# nusense-monitors.net
KiCad netlist of a schematic drawn in Altium Designer
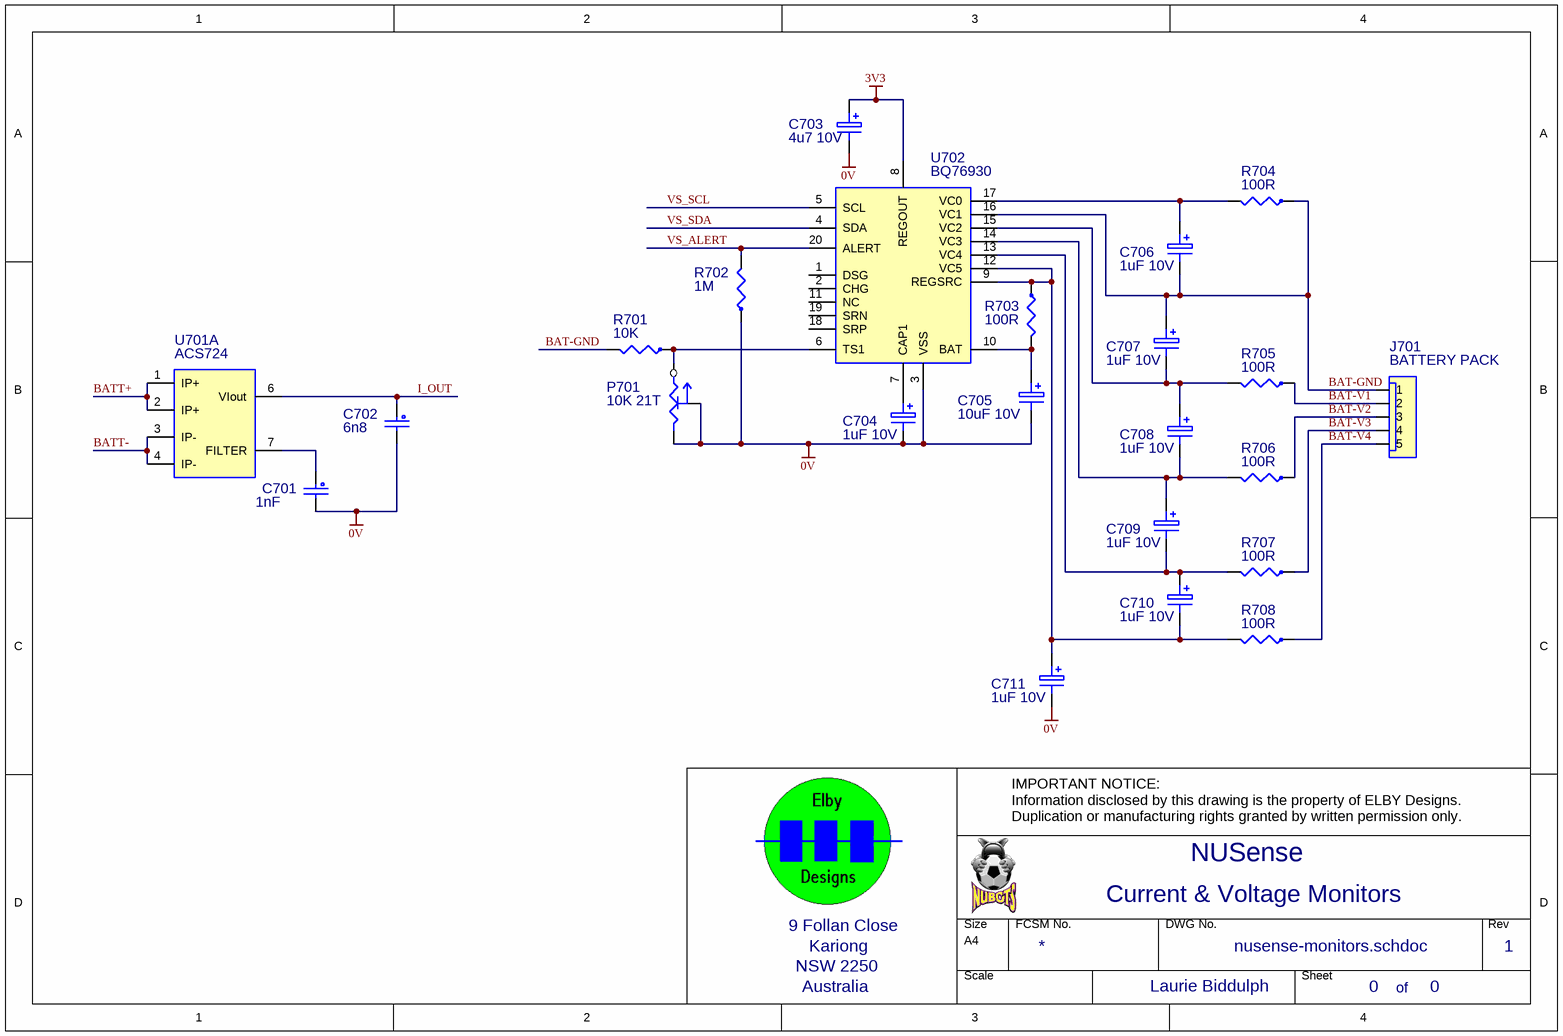
[diagram p0: nusense-monitors.schdoc]

(export (version "E")
  (design (tool "Eeschema 10.0.6"))
  (components
    (comp (ref "C701")
      (value "1nF")
      (footprint "RAD-0.2(LB)")
      (description "63V 10% Metallised Polyester")
      (libsource (lib "capacitor") (part "CP-1NF(LB)"))
    )
    (comp (ref "C702")
      (value "6n8")
      (footprint "RAD-0.2(LB)")
      (description "63V 10% Metallised Polyester")
      (libsource (lib "capacitor") (part "CP-6N8F(LB)"))
    )
    (comp (ref "C703")
      (value "4u7 10V")
      (footprint "RB-D5.0-P2.0")
      (description "20% 50V Aluminium Electrolytic")
      (libsource (lib "capacitor") (part "CE-4U7F50V(LB)"))
    )
    (comp (ref "C704")
      (value "1uF 10V")
      (footprint "RB-D5.0-P2.0")
      (description "20% 50V Aluminium Electrolytic")
      (libsource (lib "capacitor") (part "CE-1UF50V(LB)"))
    )
    (comp (ref "C705")
      (value "10uF 10V")
      (footprint "RB-D6.3-P2.5")
      (description "20% 50V Aluminium Electrolytic")
      (libsource (lib "capacitor") (part "CE-10UF50V(LB)"))
    )
    (comp (ref "C706")
      (value "1uF 10V")
      (footprint "RB-D5.0-P2.0")
      (description "20% 50V Aluminium Electrolytic")
      (libsource (lib "capacitor") (part "CE-1UF50V(LB)"))
    )
    (comp (ref "C707")
      (value "1uF 10V")
      (footprint "RB-D5.0-P2.0")
      (description "20% 50V Aluminium Electrolytic")
      (libsource (lib "capacitor") (part "CE-1UF50V(LB)"))
    )
    (comp (ref "C708")
      (value "1uF 10V")
      (footprint "RB-D5.0-P2.0")
      (description "20% 50V Aluminium Electrolytic")
      (libsource (lib "capacitor") (part "CE-1UF50V(LB)"))
    )
    (comp (ref "C709")
      (value "1uF 10V")
      (footprint "RB-D5.0-P2.0")
      (description "20% 50V Aluminium Electrolytic")
      (libsource (lib "capacitor") (part "CE-1UF50V(LB)"))
    )
    (comp (ref "C710")
      (value "1uF 10V")
      (footprint "RB-D5.0-P2.0")
      (description "20% 50V Aluminium Electrolytic")
      (libsource (lib "capacitor") (part "CE-1UF50V(LB)"))
    )
    (comp (ref "C711")
      (value "1uF 10V")
      (footprint "RB-D5.0-P2.0")
      (description "20% 50V Aluminium Electrolytic")
      (libsource (lib "capacitor") (part "CE-1UF50V(LB)"))
    )
    (comp (ref "J701")
      (value "BATTERY PACK")
      (footprint "MTA-5V(LB)")
      (libsource (lib "connectors") (part "MTA-5V(LB)"))
    )
    (comp (ref "P701")
      (value "10K 21T")
      (footprint "TRIMPOT(LB)")
      (description "Multiturn Trimpot (Spectrol 64W)")
      (libsource (lib "potentiometer") (part "RT-10K(LB)"))
    )
    (comp (ref "R701")
      (value "10K")
      (footprint "AXIAL-0.4(LB)")
      (description "0.5W 1% Metal Film Resistor")
      (libsource (lib "resistor") (part "RM-10K(LB)"))
    )
    (comp (ref "R702")
      (value "1M")
      (footprint "AXIAL-0.4(LB)")
      (description "0.5W 1% Metal Film Resistor")
      (libsource (lib "resistor") (part "RM-1M(LB)"))
    )
    (comp (ref "R703")
      (value "100R")
      (footprint "AXIAL-0.4(LB)")
      (description "0.5W 1% Metal Film Resistor")
      (libsource (lib "resistor") (part "RM-100R(LB)"))
    )
    (comp (ref "R704")
      (value "100R")
      (footprint "AXIAL-0.4(LB)")
      (description "0.5W 1% Metal Film Resistor")
      (libsource (lib "resistor") (part "RM-100R(LB)"))
    )
    (comp (ref "R705")
      (value "100R")
      (footprint "AXIAL-0.4(LB)")
      (description "0.5W 1% Metal Film Resistor")
      (libsource (lib "resistor") (part "RM-100R(LB)"))
    )
    (comp (ref "R706")
      (value "100R")
      (footprint "AXIAL-0.4(LB)")
      (description "0.5W 1% Metal Film Resistor")
      (libsource (lib "resistor") (part "RM-100R(LB)"))
    )
    (comp (ref "R707")
      (value "100R")
      (footprint "AXIAL-0.4(LB)")
      (description "0.5W 1% Metal Film Resistor")
      (libsource (lib "resistor") (part "RM-100R(LB)"))
    )
    (comp (ref "R708")
      (value "100R")
      (footprint "AXIAL-0.4(LB)")
      (description "0.5W 1% Metal Film Resistor")
      (libsource (lib "resistor") (part "RM-100R(LB)"))
    )
    (comp (ref "U701")
      (value "ACS724")
      (description "Current Monitor")
      (libsource (lib "NuBots") (part "ACS724"))
    )
    (comp (ref "U702")
      (value "BQ76930")
      (description "Battery Monitor")
      (libsource (lib "NuBots") (part "BQ76930"))
    )
  )
  (nets
    (net (code "1") (name "/BAT-GND") (class "Default")
      (node (ref "C706") (pin "2") (pintype "passive"))
      (node (ref "C707") (pin "1") (pintype "passive"))
      (node (ref "J701") (pin "1") (pinfunction "1_1") (pintype "passive"))
      (node (ref "R701") (pin "2") (pinfunction "2_2") (pintype "passive"))
      (node (ref "R704") (pin "1") (pinfunction "1_1") (pintype "passive"))
      (node (ref "U702") (pin "16") (pinfunction "VC1_16") (pintype "passive"))
    )
    (net (code "2") (name "/BAT-V1") (class "Default")
      (node (ref "J701") (pin "2") (pinfunction "2_2") (pintype "passive"))
      (node (ref "R705") (pin "1") (pinfunction "1_1") (pintype "passive"))
    )
    (net (code "3") (name "/BAT-V2") (class "Default")
      (node (ref "J701") (pin "3") (pinfunction "3_3") (pintype "passive"))
      (node (ref "R706") (pin "1") (pinfunction "1_1") (pintype "passive"))
    )
    (net (code "4") (name "/BAT-V3") (class "Default")
      (node (ref "J701") (pin "4") (pinfunction "4_4") (pintype "passive"))
      (node (ref "R707") (pin "1") (pinfunction "1_1") (pintype "passive"))
    )
    (net (code "5") (name "/BAT-V4") (class "Default")
      (node (ref "J701") (pin "5") (pinfunction "5_5") (pintype "passive"))
      (node (ref "R708") (pin "1") (pinfunction "1_1") (pintype "passive"))
    )
    (net (code "6") (name "/BATT+") (class "Default")
      (node (ref "U701") (pin "1") (pinfunction "IP+_1") (pintype "passive"))
      (node (ref "U701") (pin "2") (pinfunction "IP+_2") (pintype "passive"))
    )
    (net (code "7") (name "/BATT-") (class "Default")
      (node (ref "U701") (pin "3") (pinfunction "IP-_3") (pintype "passive"))
      (node (ref "U701") (pin "4") (pinfunction "IP-_4") (pintype "passive"))
    )
    (net (code "8") (name "/I_OUT") (class "Default")
      (node (ref "C702") (pin "1") (pintype "passive"))
      (node (ref "U701") (pin "6") (pinfunction "VIout_6") (pintype "passive"))
    )
    (net (code "9") (name "/VS_ALERT") (class "Default")
      (node (ref "R702") (pin "2") (pinfunction "2_2") (pintype "passive"))
      (node (ref "U702") (pin "20") (pinfunction "ALERT_20") (pintype "passive"))
    )
    (net (code "10") (name "/VS_SCL") (class "Default")
      (node (ref "U702") (pin "5") (pinfunction "SCL_5") (pintype "passive"))
    )
    (net (code "11") (name "/VS_SDA") (class "Default")
      (node (ref "U702") (pin "4") (pinfunction "SDA_4") (pintype "passive"))
    )
    (net (code "12") (name "0V") (class "Default")
      (node (ref "C701") (pin "2") (pintype "passive"))
      (node (ref "C702") (pin "2") (pintype "passive"))
      (node (ref "C703") (pin "2") (pintype "passive"))
      (node (ref "C704") (pin "2") (pintype "passive"))
      (node (ref "C705") (pin "2") (pintype "passive"))
      (node (ref "C711") (pin "2") (pintype "passive"))
      (node (ref "P701") (pin "1") (pinfunction "A_1") (pintype "passive"))
      (node (ref "P701") (pin "2") (pinfunction "W_2") (pintype "passive"))
      (node (ref "R702") (pin "1") (pinfunction "1_1") (pintype "passive"))
      (node (ref "U702") (pin "3") (pinfunction "VSS_3") (pintype "passive"))
    )
    (net (code "13") (name "3V3") (class "Default")
      (node (ref "C703") (pin "1") (pintype "passive"))
      (node (ref "U702") (pin "8") (pinfunction "REGOUT_8") (pintype "passive"))
    )
    (net (code "14") (name "Net-(P701-C)") (class "Default")
      (node (ref "P701") (pin "3") (pinfunction "C_3") (pintype "passive"))
      (node (ref "R701") (pin "1") (pinfunction "1_1") (pintype "passive"))
      (node (ref "U702") (pin "6") (pinfunction "TS1_6") (pintype "passive"))
    )
    (net (code "15") (name "Net-(U701A-FILTER)") (class "Default")
      (node (ref "C701") (pin "1") (pintype "passive"))
      (node (ref "U701") (pin "7") (pinfunction "FILTER_7") (pintype "passive"))
    )
    (net (code "16") (name "Net-(U702-BAT)") (class "Default")
      (node (ref "C705") (pin "1") (pintype "passive"))
      (node (ref "R703") (pin "2") (pinfunction "2_2") (pintype "passive"))
      (node (ref "U702") (pin "10") (pinfunction "BAT_10") (pintype "passive"))
    )
    (net (code "17") (name "Net-(U702-CAP1)") (class "Default")
      (node (ref "C704") (pin "1") (pintype "passive"))
      (node (ref "U702") (pin "7") (pinfunction "CAP1_7") (pintype "passive"))
    )
    (net (code "18") (name "Net-(U702-REGSRC)") (class "Default")
      (node (ref "C710") (pin "2") (pintype "passive"))
      (node (ref "C711") (pin "1") (pintype "passive"))
      (node (ref "R703") (pin "1") (pinfunction "1_1") (pintype "passive"))
      (node (ref "R708") (pin "2") (pinfunction "2_2") (pintype "passive"))
      (node (ref "U702") (pin "12") (pinfunction "VC5_12") (pintype "passive"))
      (node (ref "U702") (pin "9") (pinfunction "REGSRC_9") (pintype "passive"))
    )
    (net (code "19") (name "Net-(U702-VC0)") (class "Default")
      (node (ref "C706") (pin "1") (pintype "passive"))
      (node (ref "R704") (pin "2") (pinfunction "2_2") (pintype "passive"))
      (node (ref "U702") (pin "17") (pinfunction "VC0_17") (pintype "passive"))
    )
    (net (code "20") (name "Net-(U702-VC2)") (class "Default")
      (node (ref "C707") (pin "2") (pintype "passive"))
      (node (ref "C708") (pin "1") (pintype "passive"))
      (node (ref "R705") (pin "2") (pinfunction "2_2") (pintype "passive"))
      (node (ref "U702") (pin "15") (pinfunction "VC2_15") (pintype "passive"))
    )
    (net (code "21") (name "Net-(U702-VC3)") (class "Default")
      (node (ref "C708") (pin "2") (pintype "passive"))
      (node (ref "C709") (pin "1") (pintype "passive"))
      (node (ref "R706") (pin "2") (pinfunction "2_2") (pintype "passive"))
      (node (ref "U702") (pin "14") (pinfunction "VC3_14") (pintype "passive"))
    )
    (net (code "22") (name "Net-(U702-VC4)") (class "Default")
      (node (ref "C709") (pin "2") (pintype "passive"))
      (node (ref "C710") (pin "1") (pintype "passive"))
      (node (ref "R707") (pin "2") (pinfunction "2_2") (pintype "passive"))
      (node (ref "U702") (pin "13") (pinfunction "VC4_13") (pintype "passive"))
    )
    (net (code "23") (name "unconnected-(U702-CHG-Pad2)") (class "Default")
      (node (ref "U702") (pin "2") (pinfunction "CHG_2") (pintype "passive"))
    )
    (net (code "24") (name "unconnected-(U702-DSG-Pad1)") (class "Default")
      (node (ref "U702") (pin "1") (pinfunction "DSG_1") (pintype "passive"))
    )
    (net (code "25") (name "unconnected-(U702-NC-Pad11)") (class "Default")
      (node (ref "U702") (pin "11") (pinfunction "NC_11") (pintype "passive"))
    )
    (net (code "26") (name "unconnected-(U702-SRN-Pad19)") (class "Default")
      (node (ref "U702") (pin "19") (pinfunction "SRN_19") (pintype "passive"))
    )
    (net (code "27") (name "unconnected-(U702-SRP-Pad18)") (class "Default")
      (node (ref "U702") (pin "18") (pinfunction "SRP_18") (pintype "passive"))
    )
  )
)
